# Integrated_Board_v2.net
KiCad netlist of a schematic drawn in EAGLE
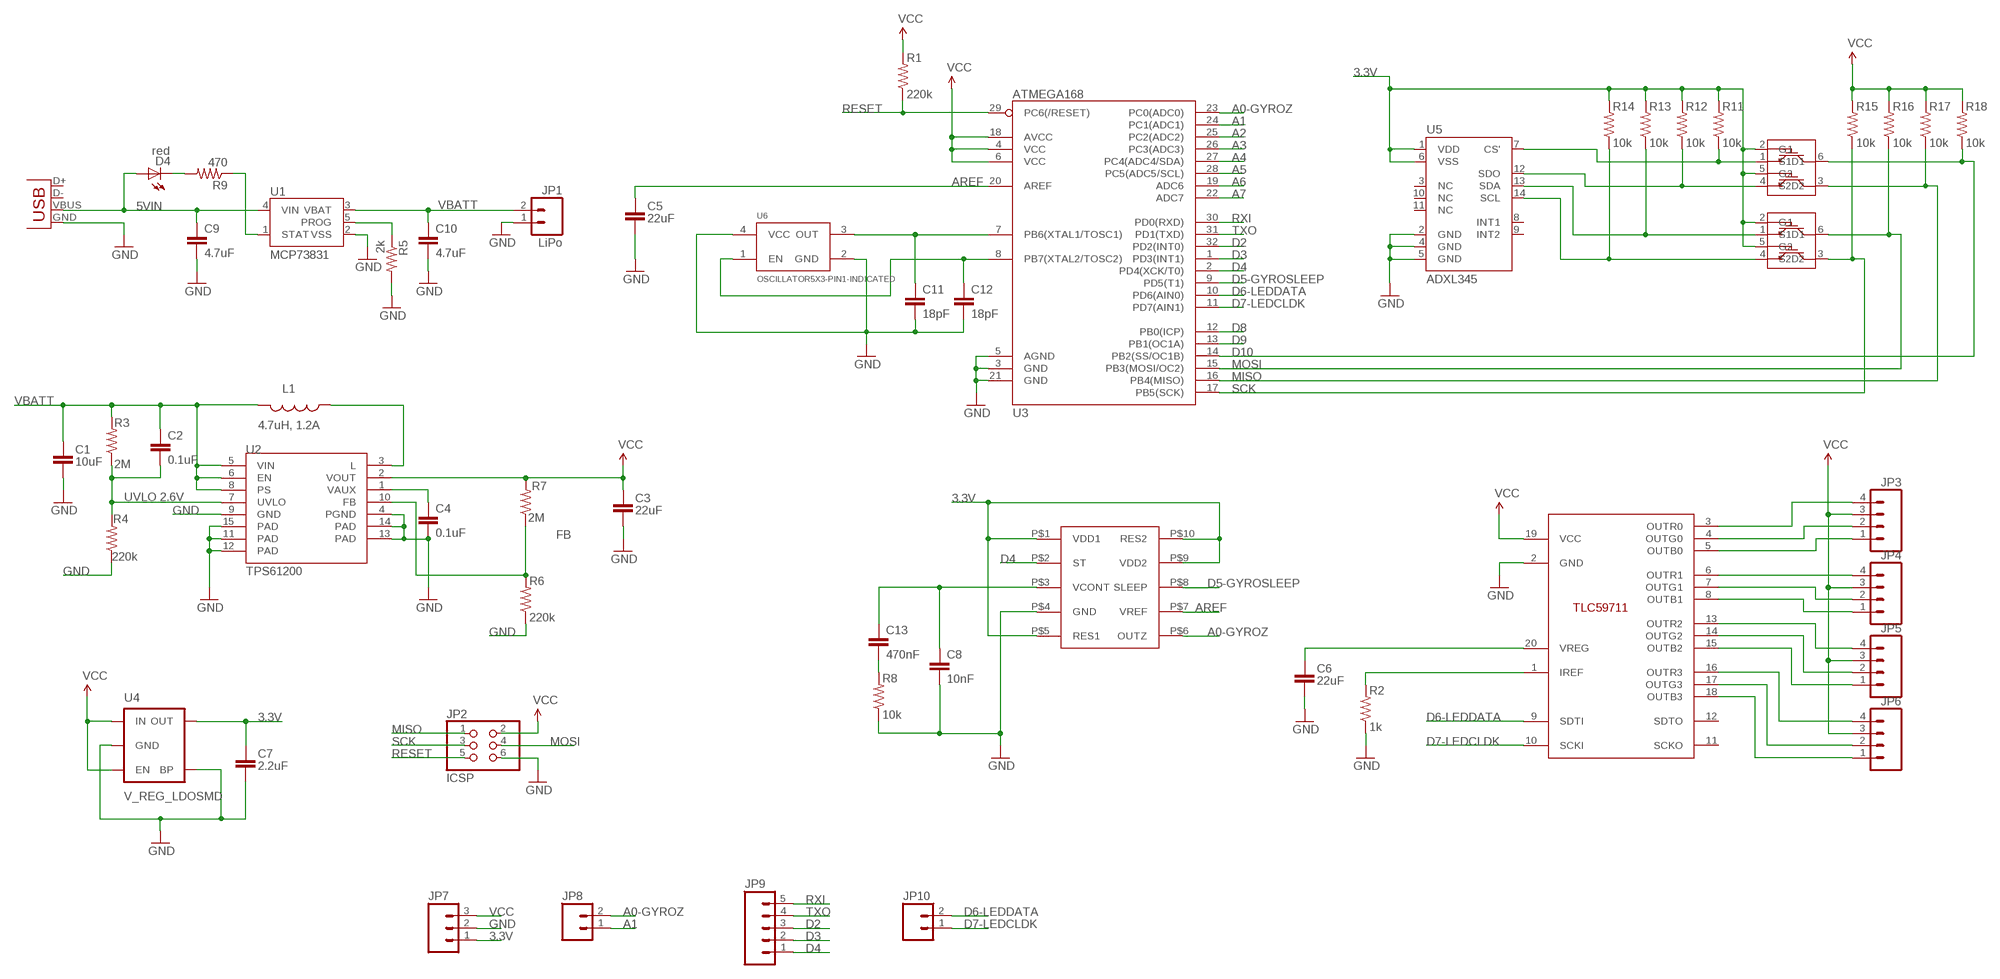
[diagram p0: schematic, sheet 1]

(export (version "E")
  (design (tool "Eeschema 10.0.6"))
  (components
    (comp (ref "C1")
      (value "10uF")
      (footprint "eagle-import:0603")
      (libsource (lib "eagle-import") (part "CAP0603"))
    )
    (comp (ref "C2")
      (value "0.1uF")
      (footprint "eagle-import:0603-CAP")
      (libsource (lib "eagle-import") (part "CAP0603-CAP"))
    )
    (comp (ref "C3")
      (value "22uF")
      (footprint "eagle-import:0805")
      (libsource (lib "eagle-import") (part "CAP0805"))
    )
    (comp (ref "C4")
      (value "0.1uF")
      (footprint "eagle-import:0603-CAP")
      (libsource (lib "eagle-import") (part "CAP0603-CAP"))
    )
    (comp (ref "C5")
      (value "22uF")
      (footprint "eagle-import:0805")
      (libsource (lib "eagle-import") (part "CAP0805"))
    )
    (comp (ref "C6")
      (value "22uF")
      (footprint "eagle-import:0805")
      (libsource (lib "eagle-import") (part "CAP0805"))
    )
    (comp (ref "C7")
      (value "2.2uF")
      (footprint "eagle-import:0603")
      (libsource (lib "eagle-import") (part "CAP0603"))
    )
    (comp (ref "C8")
      (value "10nF")
      (footprint "eagle-import:0603-CAP")
      (libsource (lib "eagle-import") (part "CAP0603-CAP"))
    )
    (comp (ref "C9")
      (value "4.7uF")
      (footprint "eagle-import:0603-CAP")
      (libsource (lib "eagle-import") (part "CAP0603-CAP"))
    )
    (comp (ref "C10")
      (value "4.7uF")
      (footprint "eagle-import:0603-CAP")
      (libsource (lib "eagle-import") (part "CAP0603-CAP"))
    )
    (comp (ref "C11")
      (value "18pF")
      (footprint "eagle-import:0603-CAP")
      (libsource (lib "eagle-import") (part "CAP0603-CAP"))
    )
    (comp (ref "C12")
      (value "18pF")
      (footprint "eagle-import:0603-CAP")
      (libsource (lib "eagle-import") (part "CAP0603-CAP"))
    )
    (comp (ref "C13")
      (value "470nF")
      (footprint "eagle-import:0603-CAP")
      (libsource (lib "eagle-import") (part "CAP0603-CAP"))
    )
    (comp (ref "D4")
      (value "red")
      (footprint "eagle-import:LED-0603")
      (libsource (lib "eagle-import") (part "LED0603"))
    )
    (comp (ref "JP1")
      (value "LiPo")
      (footprint "eagle-import:JST-2-SMD")
      (libsource (lib "eagle-import") (part "M02-JST-2MM-SMT"))
    )
    (comp (ref "JP2")
      (value "ICSP")
      (footprint "eagle-import:2X03")
      (libsource (lib "eagle-import") (part "PINHD-2X3"))
    )
    (comp (ref "JP3")
      (value "M04PTH")
      (footprint "eagle-import:1X04")
      (libsource (lib "eagle-import") (part "M04PTH"))
    )
    (comp (ref "JP4")
      (value "M04PTH")
      (footprint "eagle-import:1X04")
      (libsource (lib "eagle-import") (part "M04PTH"))
    )
    (comp (ref "JP5")
      (value "M04PTH")
      (footprint "eagle-import:1X04")
      (libsource (lib "eagle-import") (part "M04PTH"))
    )
    (comp (ref "JP6")
      (value "M04PTH")
      (footprint "eagle-import:1X04")
      (libsource (lib "eagle-import") (part "M04PTH"))
    )
    (comp (ref "JP7")
      (value "M03PTH")
      (footprint "eagle-import:1X03")
      (libsource (lib "eagle-import") (part "M03PTH"))
    )
    (comp (ref "JP8")
      (value "M02PTH")
      (footprint "eagle-import:1X02")
      (libsource (lib "eagle-import") (part "M02PTH"))
    )
    (comp (ref "JP9")
      (value "M05PTH")
      (footprint "eagle-import:1X05")
      (libsource (lib "eagle-import") (part "M05PTH"))
    )
    (comp (ref "JP10")
      (value "M02PTH")
      (footprint "eagle-import:1X02")
      (libsource (lib "eagle-import") (part "M02PTH"))
    )
    (comp (ref "L1")
      (value "4.7uH, 1.2A")
      (footprint "eagle-import:CDRH2D09")
      (libsource (lib "eagle-import") (part "INDUCTOR."))
    )
    (comp (ref "R1")
      (value "220k")
      (footprint "eagle-import:0603-RES")
      (libsource (lib "eagle-import") (part "RESISTOR0603-RES"))
    )
    (comp (ref "R2")
      (value "1k")
      (footprint "eagle-import:0603-RES")
      (libsource (lib "eagle-import") (part "RESISTOR0603-RES"))
    )
    (comp (ref "R3")
      (value "2M")
      (footprint "eagle-import:0603-RES")
      (libsource (lib "eagle-import") (part "RESISTOR0603-RES"))
    )
    (comp (ref "R4")
      (value "220k")
      (footprint "eagle-import:0603-RES")
      (libsource (lib "eagle-import") (part "RESISTOR0603-RES"))
    )
    (comp (ref "R5")
      (value "2k")
      (footprint "eagle-import:0603-RES")
      (libsource (lib "eagle-import") (part "RESISTOR0603-RES"))
    )
    (comp (ref "R6")
      (value "220k")
      (footprint "eagle-import:0603-RES")
      (libsource (lib "eagle-import") (part "RESISTOR0603-RES"))
    )
    (comp (ref "R7")
      (value "2M")
      (footprint "eagle-import:0603-RES")
      (libsource (lib "eagle-import") (part "RESISTOR0603-RES"))
    )
    (comp (ref "R8")
      (value "10k")
      (footprint "eagle-import:0603-RES")
      (libsource (lib "eagle-import") (part "RESISTOR0603-RES"))
    )
    (comp (ref "R9")
      (value "470")
      (footprint "eagle-import:0603-RES")
      (libsource (lib "eagle-import") (part "RESISTOR0603-RES"))
    )
    (comp (ref "R11")
      (value "10k")
      (footprint "eagle-import:0603-RES")
      (libsource (lib "eagle-import") (part "RESISTOR0603-RES"))
    )
    (comp (ref "R12")
      (value "10k")
      (footprint "eagle-import:0603-RES")
      (libsource (lib "eagle-import") (part "RESISTOR0603-RES"))
    )
    (comp (ref "R13")
      (value "10k")
      (footprint "eagle-import:0603-RES")
      (libsource (lib "eagle-import") (part "RESISTOR0603-RES"))
    )
    (comp (ref "R14")
      (value "10k")
      (footprint "eagle-import:0603-RES")
      (libsource (lib "eagle-import") (part "RESISTOR0603-RES"))
    )
    (comp (ref "R15")
      (value "10k")
      (footprint "eagle-import:0603-RES")
      (libsource (lib "eagle-import") (part "RESISTOR0603-RES"))
    )
    (comp (ref "R16")
      (value "10k")
      (footprint "eagle-import:0603-RES")
      (libsource (lib "eagle-import") (part "RESISTOR0603-RES"))
    )
    (comp (ref "R17")
      (value "10k")
      (footprint "eagle-import:0603-RES")
      (libsource (lib "eagle-import") (part "RESISTOR0603-RES"))
    )
    (comp (ref "R18")
      (value "10k")
      (footprint "eagle-import:0603-RES")
      (libsource (lib "eagle-import") (part "RESISTOR0603-RES"))
    )
    (comp (ref "U$1")
      (value "TLC59711")
      (footprint "eagle-import:TSSOP20")
      (libsource (lib "eagle-import") (part "TLC59711"))
    )
    (comp (ref "U$2")
      (value "2N7002DW")
      (footprint "eagle-import:SOT363")
      (libsource (lib "eagle-import") (part "2N7002DW"))
    )
    (comp (ref "U$3")
      (value "2N7002DW")
      (footprint "eagle-import:SOT363")
      (libsource (lib "eagle-import") (part "2N7002DW"))
    )
    (comp (ref "U$4")
      (value "LY3100ALH")
      (footprint "eagle-import:LGA10")
      (libsource (lib "eagle-import") (part "LY3100ALH"))
    )
    (comp (ref "U1")
      (value "MCP73831")
      (footprint "eagle-import:SOT23-5")
      (libsource (lib "eagle-import") (part "MCP73831"))
    )
    (comp (ref "U2")
      (value "TPS61200")
      (footprint "eagle-import:QFN-10_PAD")
      (libsource (lib "eagle-import") (part "TPS61200"))
    )
    (comp (ref "U3")
      (value "ATMEGA168")
      (footprint "eagle-import:TQFP32-08")
      (libsource (lib "eagle-import") (part "ATMEGA168"))
    )
    (comp (ref "U4")
      (value "V_REG_LDOSMD")
      (footprint "eagle-import:SOT23-5")
      (libsource (lib "eagle-import") (part "V_REG_LDOSMD"))
    )
    (comp (ref "U5")
      (value "ADXL345")
      (footprint "eagle-import:LGA14")
      (libsource (lib "eagle-import") (part "ADXL345"))
    )
    (comp (ref "U6")
      (value "OSCILLATOR5X3-PIN1-INDICATED")
      (footprint "eagle-import:CRYSTAL-OSC-SMD-5X3")
      (libsource (lib "eagle-import") (part "OSCILLATOR5X3-PIN1-INDICATED"))
    )
    (comp (ref "X1")
      (value "USB-MICROB")
      (footprint "eagle-import:USB-MICROB")
      (libsource (lib "eagle-import") (part "USB-MICROB"))
    )
  )
  (nets
    (net (code "1") (name "/3.3V") (class "Default")
      (node (ref "C7") (pin "1") (pinfunction "1_1") (pintype "passive"))
      (node (ref "JP7") (pin "1") (pinfunction "1_1") (pintype "passive"))
      (node (ref "R11") (pin "2") (pinfunction "2_2") (pintype "passive"))
      (node (ref "R12") (pin "2") (pinfunction "2_2") (pintype "passive"))
      (node (ref "R13") (pin "2") (pinfunction "2_2") (pintype "passive"))
      (node (ref "R14") (pin "2") (pinfunction "2_2") (pintype "passive"))
      (node (ref "U$2") (pin "2") (pinfunction "G1_2") (pintype "bidirectional"))
      (node (ref "U$2") (pin "5") (pinfunction "G2_5") (pintype "bidirectional"))
      (node (ref "U$3") (pin "2") (pinfunction "G1_2") (pintype "bidirectional"))
      (node (ref "U$3") (pin "5") (pinfunction "G2_5") (pintype "bidirectional"))
      (node (ref "U$4") (pin "P$1") (pinfunction "VDD1_P$1") (pintype "bidirectional"))
      (node (ref "U$4") (pin "P$10") (pinfunction "RES2_P$10") (pintype "bidirectional"))
      (node (ref "U$4") (pin "P$5") (pinfunction "RES1_P$5") (pintype "bidirectional"))
      (node (ref "U$4") (pin "P$9") (pinfunction "VDD2_P$9") (pintype "bidirectional"))
      (node (ref "U4") (pin "5") (pinfunction "OUT_5") (pintype "passive"))
      (node (ref "U5") (pin "1") (pinfunction "VDD_1") (pintype "bidirectional"))
      (node (ref "U5") (pin "6") (pinfunction "VSS_6") (pintype "bidirectional"))
    )
    (net (code "2") (name "/5VIN") (class "Default")
      (node (ref "C9") (pin "1") (pinfunction "1_1") (pintype "passive"))
      (node (ref "D4") (pin "A") (pinfunction "A_A") (pintype "passive"))
      (node (ref "U1") (pin "4") (pinfunction "VIN_4") (pintype "power_in"))
      (node (ref "X1") (pin "VBUS") (pinfunction "VBUS_VBUS") (pintype "bidirectional"))
    )
    (net (code "3") (name "/A0-GYROZ") (class "Default")
      (node (ref "JP8") (pin "2") (pinfunction "2_2") (pintype "passive"))
      (node (ref "U$4") (pin "P$6") (pinfunction "OUTZ_P$6") (pintype "bidirectional"))
      (node (ref "U3") (pin "23") (pinfunction "PC0(ADC0)_23") (pintype "bidirectional"))
    )
    (net (code "4") (name "/A1") (class "Default")
      (node (ref "JP8") (pin "1") (pinfunction "1_1") (pintype "passive"))
      (node (ref "U3") (pin "24") (pinfunction "PC1(ADC1)_24") (pintype "bidirectional"))
    )
    (net (code "5") (name "/A2") (class "Default")
      (node (ref "U3") (pin "25") (pinfunction "PC2(ADC2)_25") (pintype "bidirectional"))
    )
    (net (code "6") (name "/A3") (class "Default")
      (node (ref "U3") (pin "26") (pinfunction "PC3(ADC3)_26") (pintype "bidirectional"))
    )
    (net (code "7") (name "/A4") (class "Default")
      (node (ref "U3") (pin "27") (pinfunction "PC4(ADC4/SDA)_27") (pintype "bidirectional"))
    )
    (net (code "8") (name "/A5") (class "Default")
      (node (ref "U3") (pin "28") (pinfunction "PC5(ADC5/SCL)_28") (pintype "bidirectional"))
    )
    (net (code "9") (name "/A6") (class "Default")
      (node (ref "U3") (pin "19") (pinfunction "ADC6_19") (pintype "bidirectional"))
    )
    (net (code "10") (name "/A7") (class "Default")
      (node (ref "U3") (pin "22") (pinfunction "ADC7_22") (pintype "bidirectional"))
    )
    (net (code "11") (name "/AREF") (class "Default")
      (node (ref "C5") (pin "1") (pinfunction "1_1") (pintype "passive"))
      (node (ref "U$4") (pin "P$7") (pinfunction "VREF_P$7") (pintype "bidirectional"))
      (node (ref "U3") (pin "20") (pinfunction "AREF_20") (pintype "bidirectional"))
    )
    (net (code "12") (name "/D2") (class "Default")
      (node (ref "JP9") (pin "3") (pinfunction "3_3") (pintype "passive"))
      (node (ref "U3") (pin "32") (pinfunction "PD2(INT0)_32") (pintype "bidirectional"))
    )
    (net (code "13") (name "/D3") (class "Default")
      (node (ref "JP9") (pin "2") (pinfunction "2_2") (pintype "passive"))
      (node (ref "U3") (pin "1") (pinfunction "PD3(INT1)_1") (pintype "bidirectional"))
    )
    (net (code "14") (name "/D4") (class "Default")
      (node (ref "JP9") (pin "1") (pinfunction "1_1") (pintype "passive"))
      (node (ref "U$4") (pin "P$2") (pinfunction "ST_P$2") (pintype "bidirectional"))
      (node (ref "U3") (pin "2") (pinfunction "PD4(XCK/T0)_2") (pintype "bidirectional"))
    )
    (net (code "15") (name "/D5-GYROSLEEP") (class "Default")
      (node (ref "U$4") (pin "P$8") (pinfunction "SLEEP_P$8") (pintype "bidirectional"))
      (node (ref "U3") (pin "9") (pinfunction "PD5(T1)_9") (pintype "bidirectional"))
    )
    (net (code "16") (name "/D6-LEDDATA") (class "Default")
      (node (ref "JP10") (pin "2") (pinfunction "2_2") (pintype "passive"))
      (node (ref "U$1") (pin "9") (pinfunction "SDTI_9") (pintype "bidirectional"))
      (node (ref "U3") (pin "10") (pinfunction "PD6(AIN0)_10") (pintype "bidirectional"))
    )
    (net (code "17") (name "/D7-LEDCLDK") (class "Default")
      (node (ref "JP10") (pin "1") (pinfunction "1_1") (pintype "passive"))
      (node (ref "U$1") (pin "10") (pinfunction "SCKI_10") (pintype "bidirectional"))
      (node (ref "U3") (pin "11") (pinfunction "PD7(AIN1)_11") (pintype "bidirectional"))
    )
    (net (code "18") (name "/D8") (class "Default")
      (node (ref "U3") (pin "12") (pinfunction "PB0(ICP)_12") (pintype "bidirectional"))
    )
    (net (code "19") (name "/D9") (class "Default")
      (node (ref "U3") (pin "13") (pinfunction "PB1(OC1A)_13") (pintype "bidirectional"))
    )
    (net (code "20") (name "/D10") (class "Default")
      (node (ref "R18") (pin "1") (pinfunction "1_1") (pintype "passive"))
      (node (ref "U$2") (pin "6") (pinfunction "D1_6") (pintype "bidirectional"))
      (node (ref "U3") (pin "14") (pinfunction "PB2(SS/OC1B)_14") (pintype "bidirectional"))
    )
    (net (code "21") (name "/FB") (class "Default")
      (node (ref "R6") (pin "2") (pinfunction "2_2") (pintype "passive"))
      (node (ref "R7") (pin "1") (pinfunction "1_1") (pintype "passive"))
      (node (ref "U2") (pin "10") (pinfunction "FB_10") (pintype "passive"))
    )
    (net (code "22") (name "/MISO") (class "Default")
      (node (ref "JP2") (pin "1") (pinfunction "1_1") (pintype "passive"))
      (node (ref "R17") (pin "1") (pinfunction "1_1") (pintype "passive"))
      (node (ref "U$2") (pin "3") (pinfunction "D2_3") (pintype "bidirectional"))
      (node (ref "U3") (pin "16") (pinfunction "PB4(MISO)_16") (pintype "bidirectional"))
    )
    (net (code "23") (name "/MOSI") (class "Default")
      (node (ref "JP2") (pin "4") (pinfunction "4_4") (pintype "passive"))
      (node (ref "R16") (pin "1") (pinfunction "1_1") (pintype "passive"))
      (node (ref "U$3") (pin "6") (pinfunction "D1_6") (pintype "bidirectional"))
      (node (ref "U3") (pin "15") (pinfunction "PB3(MOSI/OC2)_15") (pintype "bidirectional"))
    )
    (net (code "24") (name "/RESET") (class "Default")
      (node (ref "JP2") (pin "5") (pinfunction "5_5") (pintype "passive"))
      (node (ref "R1") (pin "1") (pinfunction "1_1") (pintype "passive"))
      (node (ref "U3") (pin "29") (pinfunction "PC6(/RESET)_29") (pintype "bidirectional"))
    )
    (net (code "25") (name "/RXI") (class "Default")
      (node (ref "JP9") (pin "5") (pinfunction "5_5") (pintype "passive"))
      (node (ref "U3") (pin "30") (pinfunction "PD0(RXD)_30") (pintype "bidirectional"))
    )
    (net (code "26") (name "/SCK") (class "Default")
      (node (ref "JP2") (pin "3") (pinfunction "3_3") (pintype "passive"))
      (node (ref "R15") (pin "1") (pinfunction "1_1") (pintype "passive"))
      (node (ref "U$3") (pin "3") (pinfunction "D2_3") (pintype "bidirectional"))
      (node (ref "U3") (pin "17") (pinfunction "PB5(SCK)_17") (pintype "bidirectional"))
    )
    (net (code "27") (name "/TXO") (class "Default")
      (node (ref "JP9") (pin "4") (pinfunction "4_4") (pintype "passive"))
      (node (ref "U3") (pin "31") (pinfunction "PD1(TXD)_31") (pintype "bidirectional"))
    )
    (net (code "28") (name "/VBATT") (class "Default")
      (node (ref "C1") (pin "1") (pinfunction "1_1") (pintype "passive"))
      (node (ref "C10") (pin "1") (pinfunction "1_1") (pintype "passive"))
      (node (ref "C2") (pin "1") (pinfunction "1_1") (pintype "passive"))
      (node (ref "JP1") (pin "2") (pinfunction "2_2") (pintype "passive"))
      (node (ref "L1") (pin "P$2") (pinfunction "2_P$2") (pintype "passive"))
      (node (ref "R3") (pin "2") (pinfunction "2_2") (pintype "passive"))
      (node (ref "U1") (pin "3") (pinfunction "VBAT_3") (pintype "power_in"))
      (node (ref "U2") (pin "5") (pinfunction "VIN_5") (pintype "power_in"))
      (node (ref "U2") (pin "6") (pinfunction "EN_6") (pintype "input"))
      (node (ref "U2") (pin "8") (pinfunction "PS_8") (pintype "input"))
    )
    (net (code "29") (name "GND") (class "Default")
      (node (ref "C1") (pin "2") (pinfunction "2_2") (pintype "passive"))
      (node (ref "C10") (pin "2") (pinfunction "2_2") (pintype "passive"))
      (node (ref "C11") (pin "2") (pinfunction "2_2") (pintype "passive"))
      (node (ref "C12") (pin "2") (pinfunction "2_2") (pintype "passive"))
      (node (ref "C3") (pin "2") (pinfunction "2_2") (pintype "passive"))
      (node (ref "C4") (pin "2") (pinfunction "2_2") (pintype "passive"))
      (node (ref "C5") (pin "2") (pinfunction "2_2") (pintype "passive"))
      (node (ref "C6") (pin "2") (pinfunction "2_2") (pintype "passive"))
      (node (ref "C7") (pin "2") (pinfunction "2_2") (pintype "passive"))
      (node (ref "C8") (pin "2") (pinfunction "2_2") (pintype "passive"))
      (node (ref "C9") (pin "2") (pinfunction "2_2") (pintype "passive"))
      (node (ref "JP1") (pin "1") (pinfunction "1_1") (pintype "passive"))
      (node (ref "JP2") (pin "6") (pinfunction "6_6") (pintype "passive"))
      (node (ref "JP7") (pin "2") (pinfunction "2_2") (pintype "passive"))
      (node (ref "R2") (pin "1") (pinfunction "1_1") (pintype "passive"))
      (node (ref "R4") (pin "1") (pinfunction "1_1") (pintype "passive"))
      (node (ref "R5") (pin "2") (pinfunction "2_2") (pintype "passive"))
      (node (ref "R6") (pin "1") (pinfunction "1_1") (pintype "passive"))
      (node (ref "R8") (pin "1") (pinfunction "1_1") (pintype "passive"))
      (node (ref "U$1") (pin "2") (pinfunction "GND_2") (pintype "bidirectional"))
      (node (ref "U$4") (pin "P$4") (pinfunction "GND_P$4") (pintype "bidirectional"))
      (node (ref "U1") (pin "2") (pinfunction "VSS_2") (pintype "power_in"))
      (node (ref "U2") (pin "11") (pinfunction "PAD_11") (pintype "power_in"))
      (node (ref "U2") (pin "12") (pinfunction "PAD_12") (pintype "power_in"))
      (node (ref "U2") (pin "13") (pinfunction "PAD_13") (pintype "power_in"))
      (node (ref "U2") (pin "14") (pinfunction "PAD_14") (pintype "power_in"))
      (node (ref "U2") (pin "15") (pinfunction "PAD_15") (pintype "power_in"))
      (node (ref "U2") (pin "4") (pinfunction "PGND_4") (pintype "power_in"))
      (node (ref "U2") (pin "9") (pinfunction "GND_9") (pintype "power_in"))
      (node (ref "U3") (pin "21") (pinfunction "GND_21") (pintype "bidirectional"))
      (node (ref "U3") (pin "3") (pinfunction "GND_3") (pintype "bidirectional"))
      (node (ref "U3") (pin "5") (pinfunction "AGND_5") (pintype "bidirectional"))
      (node (ref "U4") (pin "2") (pinfunction "GND_2") (pintype "input"))
      (node (ref "U4") (pin "4") (pinfunction "BP_4") (pintype "input"))
      (node (ref "U5") (pin "2") (pinfunction "GND_2") (pintype "bidirectional"))
      (node (ref "U5") (pin "4") (pinfunction "GND_4") (pintype "bidirectional"))
      (node (ref "U5") (pin "5") (pinfunction "GND_5") (pintype "bidirectional"))
      (node (ref "U6") (pin "2") (pinfunction "GND_2") (pintype "bidirectional"))
      (node (ref "U6") (pin "4") (pinfunction "VCC_4") (pintype "bidirectional"))
      (node (ref "X1") (pin "GND") (pinfunction "GND_GND") (pintype "bidirectional"))
    )
    (net (code "30") (name "Net-(C13-Pad2)") (class "Default")
      (node (ref "C13") (pin "2") (pinfunction "2_2") (pintype "passive"))
      (node (ref "R8") (pin "2") (pinfunction "2_2") (pintype "passive"))
    )
    (net (code "31") (name "Net-(D4-PadC)") (class "Default")
      (node (ref "D4") (pin "C") (pinfunction "C_C") (pintype "passive"))
      (node (ref "R9") (pin "2") (pinfunction "2_2") (pintype "passive"))
    )
    (net (code "32") (name "Net-(JP3-B)") (class "Default")
      (node (ref "JP3") (pin "4") (pinfunction "B_4") (pintype "passive"))
      (node (ref "U$1") (pin "3") (pinfunction "OUTR0_3") (pintype "bidirectional"))
    )
    (net (code "33") (name "Net-(JP3-COM)") (class "Default")
      (node (ref "JP3") (pin "1") (pinfunction "COM_1") (pintype "passive"))
      (node (ref "U$1") (pin "5") (pinfunction "OUTB0_5") (pintype "bidirectional"))
    )
    (net (code "34") (name "Net-(JP3-R)") (class "Default")
      (node (ref "JP3") (pin "2") (pinfunction "R_2") (pintype "passive"))
      (node (ref "U$1") (pin "4") (pinfunction "OUTG0_4") (pintype "bidirectional"))
    )
    (net (code "35") (name "Net-(JP4-B)") (class "Default")
      (node (ref "JP4") (pin "4") (pinfunction "B_4") (pintype "passive"))
      (node (ref "U$1") (pin "6") (pinfunction "OUTR1_6") (pintype "bidirectional"))
    )
    (net (code "36") (name "Net-(JP4-COM)") (class "Default")
      (node (ref "JP4") (pin "1") (pinfunction "COM_1") (pintype "passive"))
      (node (ref "U$1") (pin "8") (pinfunction "OUTB1_8") (pintype "bidirectional"))
    )
    (net (code "37") (name "Net-(JP4-R)") (class "Default")
      (node (ref "JP4") (pin "2") (pinfunction "R_2") (pintype "passive"))
      (node (ref "U$1") (pin "7") (pinfunction "OUTG1_7") (pintype "bidirectional"))
    )
    (net (code "38") (name "Net-(JP5-B)") (class "Default")
      (node (ref "JP5") (pin "4") (pinfunction "B_4") (pintype "passive"))
      (node (ref "U$1") (pin "13") (pinfunction "OUTR2_13") (pintype "bidirectional"))
    )
    (net (code "39") (name "Net-(JP5-COM)") (class "Default")
      (node (ref "JP5") (pin "1") (pinfunction "COM_1") (pintype "passive"))
      (node (ref "U$1") (pin "15") (pinfunction "OUTB2_15") (pintype "bidirectional"))
    )
    (net (code "40") (name "Net-(JP5-R)") (class "Default")
      (node (ref "JP5") (pin "2") (pinfunction "R_2") (pintype "passive"))
      (node (ref "U$1") (pin "14") (pinfunction "OUTG2_14") (pintype "bidirectional"))
    )
    (net (code "41") (name "Net-(JP6-B)") (class "Default")
      (node (ref "JP6") (pin "4") (pinfunction "B_4") (pintype "passive"))
      (node (ref "U$1") (pin "16") (pinfunction "OUTR3_16") (pintype "bidirectional"))
    )
    (net (code "42") (name "Net-(JP6-COM)") (class "Default")
      (node (ref "JP6") (pin "1") (pinfunction "COM_1") (pintype "passive"))
      (node (ref "U$1") (pin "18") (pinfunction "OUTB3_18") (pintype "bidirectional"))
    )
    (net (code "43") (name "Net-(JP6-R)") (class "Default")
      (node (ref "JP6") (pin "2") (pinfunction "R_2") (pintype "passive"))
      (node (ref "U$1") (pin "17") (pinfunction "OUTG3_17") (pintype "bidirectional"))
    )
    (net (code "44") (name "Net-(L1-1)") (class "Default")
      (node (ref "L1") (pin "P$1") (pinfunction "1_P$1") (pintype "passive"))
      (node (ref "U2") (pin "3") (pinfunction "L_3") (pintype "passive"))
    )
    (net (code "45") (name "Net-(U$1-IREF)") (class "Default")
      (node (ref "R2") (pin "2") (pinfunction "2_2") (pintype "passive"))
      (node (ref "U$1") (pin "1") (pinfunction "IREF_1") (pintype "bidirectional"))
    )
    (net (code "46") (name "Net-(U$1-VREG)") (class "Default")
      (node (ref "C6") (pin "1") (pinfunction "1_1") (pintype "passive"))
      (node (ref "U$1") (pin "20") (pinfunction "VREG_20") (pintype "bidirectional"))
    )
    (net (code "47") (name "Net-(U$2-S1)") (class "Default")
      (node (ref "R11") (pin "1") (pinfunction "1_1") (pintype "passive"))
      (node (ref "U$2") (pin "1") (pinfunction "S1_1") (pintype "bidirectional"))
      (node (ref "U5") (pin "7") (pinfunction "CS'_7") (pintype "bidirectional"))
    )
    (net (code "48") (name "Net-(U$2-S2)") (class "Default")
      (node (ref "R12") (pin "1") (pinfunction "1_1") (pintype "passive"))
      (node (ref "U$2") (pin "4") (pinfunction "S2_4") (pintype "bidirectional"))
      (node (ref "U5") (pin "12") (pinfunction "SDO_12") (pintype "bidirectional"))
    )
    (net (code "49") (name "Net-(U$3-S1)") (class "Default")
      (node (ref "R13") (pin "1") (pinfunction "1_1") (pintype "passive"))
      (node (ref "U$3") (pin "1") (pinfunction "S1_1") (pintype "bidirectional"))
      (node (ref "U5") (pin "13") (pinfunction "SDA_13") (pintype "bidirectional"))
    )
    (net (code "50") (name "Net-(U$3-S2)") (class "Default")
      (node (ref "R14") (pin "1") (pinfunction "1_1") (pintype "passive"))
      (node (ref "U$3") (pin "4") (pinfunction "S2_4") (pintype "bidirectional"))
      (node (ref "U5") (pin "14") (pinfunction "SCL_14") (pintype "bidirectional"))
    )
    (net (code "51") (name "Net-(U$4-VCONT)") (class "Default")
      (node (ref "C13") (pin "1") (pinfunction "1_1") (pintype "passive"))
      (node (ref "C8") (pin "1") (pinfunction "1_1") (pintype "passive"))
      (node (ref "U$4") (pin "P$3") (pinfunction "VCONT_P$3") (pintype "bidirectional"))
    )
    (net (code "52") (name "Net-(U1-PROG)") (class "Default")
      (node (ref "R5") (pin "1") (pinfunction "1_1") (pintype "passive"))
      (node (ref "U1") (pin "5") (pinfunction "PROG_5") (pintype "input"))
    )
    (net (code "53") (name "Net-(U1-STAT)") (class "Default")
      (node (ref "R9") (pin "1") (pinfunction "1_1") (pintype "passive"))
      (node (ref "U1") (pin "1") (pinfunction "STAT_1") (pintype "output"))
    )
    (net (code "54") (name "Net-(U2-UVLO)") (class "Default")
      (node (ref "C2") (pin "2") (pinfunction "2_2") (pintype "passive"))
      (node (ref "R3") (pin "1") (pinfunction "1_1") (pintype "passive"))
      (node (ref "R4") (pin "2") (pinfunction "2_2") (pintype "passive"))
      (node (ref "U2") (pin "7") (pinfunction "UVLO_7") (pintype "passive"))
    )
    (net (code "55") (name "Net-(U2-VAUX)") (class "Default")
      (node (ref "C4") (pin "1") (pinfunction "1_1") (pintype "passive"))
      (node (ref "U2") (pin "1") (pinfunction "VAUX_1") (pintype "passive"))
    )
    (net (code "56") (name "Net-(U3-PB6(XTAL1{slash}TOSC1))") (class "Default")
      (node (ref "C11") (pin "1") (pinfunction "1_1") (pintype "passive"))
      (node (ref "U3") (pin "7") (pinfunction "PB6(XTAL1/TOSC1)_7") (pintype "bidirectional"))
      (node (ref "U6") (pin "3") (pinfunction "OUT_3") (pintype "bidirectional"))
    )
    (net (code "57") (name "Net-(U3-PB7(XTAL2{slash}TOSC2))") (class "Default")
      (node (ref "C12") (pin "1") (pinfunction "1_1") (pintype "passive"))
      (node (ref "U3") (pin "8") (pinfunction "PB7(XTAL2/TOSC2)_8") (pintype "bidirectional"))
      (node (ref "U6") (pin "1") (pinfunction "EN_1") (pintype "bidirectional"))
    )
    (net (code "58") (name "VCC") (class "Default")
      (node (ref "C3") (pin "1") (pinfunction "1_1") (pintype "passive"))
      (node (ref "JP2") (pin "2") (pinfunction "2_2") (pintype "passive"))
      (node (ref "JP3") (pin "3") (pinfunction "G_3") (pintype "passive"))
      (node (ref "JP4") (pin "3") (pinfunction "G_3") (pintype "passive"))
      (node (ref "JP5") (pin "3") (pinfunction "G_3") (pintype "passive"))
      (node (ref "JP6") (pin "3") (pinfunction "G_3") (pintype "passive"))
      (node (ref "JP7") (pin "3") (pinfunction "3_3") (pintype "passive"))
      (node (ref "R1") (pin "2") (pinfunction "2_2") (pintype "passive"))
      (node (ref "R15") (pin "2") (pinfunction "2_2") (pintype "passive"))
      (node (ref "R16") (pin "2") (pinfunction "2_2") (pintype "passive"))
      (node (ref "R17") (pin "2") (pinfunction "2_2") (pintype "passive"))
      (node (ref "R18") (pin "2") (pinfunction "2_2") (pintype "passive"))
      (node (ref "R7") (pin "2") (pinfunction "2_2") (pintype "passive"))
      (node (ref "U$1") (pin "19") (pinfunction "VCC_19") (pintype "bidirectional"))
      (node (ref "U2") (pin "2") (pinfunction "VOUT_2") (pintype "passive"))
      (node (ref "U3") (pin "18") (pinfunction "AVCC_18") (pintype "bidirectional"))
      (node (ref "U3") (pin "4") (pinfunction "VCC_4") (pintype "bidirectional"))
      (node (ref "U3") (pin "6") (pinfunction "VCC_6") (pintype "bidirectional"))
      (node (ref "U4") (pin "1") (pinfunction "IN_1") (pintype "input"))
      (node (ref "U4") (pin "3") (pinfunction "EN_3") (pintype "input"))
    )
    (net (code "59") (name "unconnected-(U$1-SCKO-Pad11)") (class "Default")
      (node (ref "U$1") (pin "11") (pinfunction "SCKO_11") (pintype "bidirectional"))
    )
    (net (code "60") (name "unconnected-(U$1-SDTO-Pad12)") (class "Default")
      (node (ref "U$1") (pin "12") (pinfunction "SDTO_12") (pintype "bidirectional"))
    )
    (net (code "61") (name "unconnected-(U5-INT1-Pad8)") (class "Default")
      (node (ref "U5") (pin "8") (pinfunction "INT1_8") (pintype "bidirectional"))
    )
    (net (code "62") (name "unconnected-(U5-INT2-Pad9)") (class "Default")
      (node (ref "U5") (pin "9") (pinfunction "INT2_9") (pintype "bidirectional"))
    )
    (net (code "63") (name "unconnected-(U5-NC-Pad3)") (class "Default")
      (node (ref "U5") (pin "3") (pinfunction "NC_3") (pintype "bidirectional"))
    )
    (net (code "64") (name "unconnected-(U5-NC-Pad10)") (class "Default")
      (node (ref "U5") (pin "10") (pinfunction "NC_10") (pintype "bidirectional"))
    )
    (net (code "65") (name "unconnected-(U5-NC-Pad11)") (class "Default")
      (node (ref "U5") (pin "11") (pinfunction "NC_11") (pintype "bidirectional"))
    )
    (net (code "66") (name "unconnected-(X1-PadD+)") (class "Default")
      (node (ref "X1") (pin "D+") (pinfunction "D+_D+") (pintype "bidirectional"))
    )
    (net (code "67") (name "unconnected-(X1-PadD-)") (class "Default")
      (node (ref "X1") (pin "D-") (pinfunction "D-_D-") (pintype "bidirectional"))
    )
  )
)
